# fpga-bank4-inside.net
KiCad netlist of a schematic drawn in Altium Designer
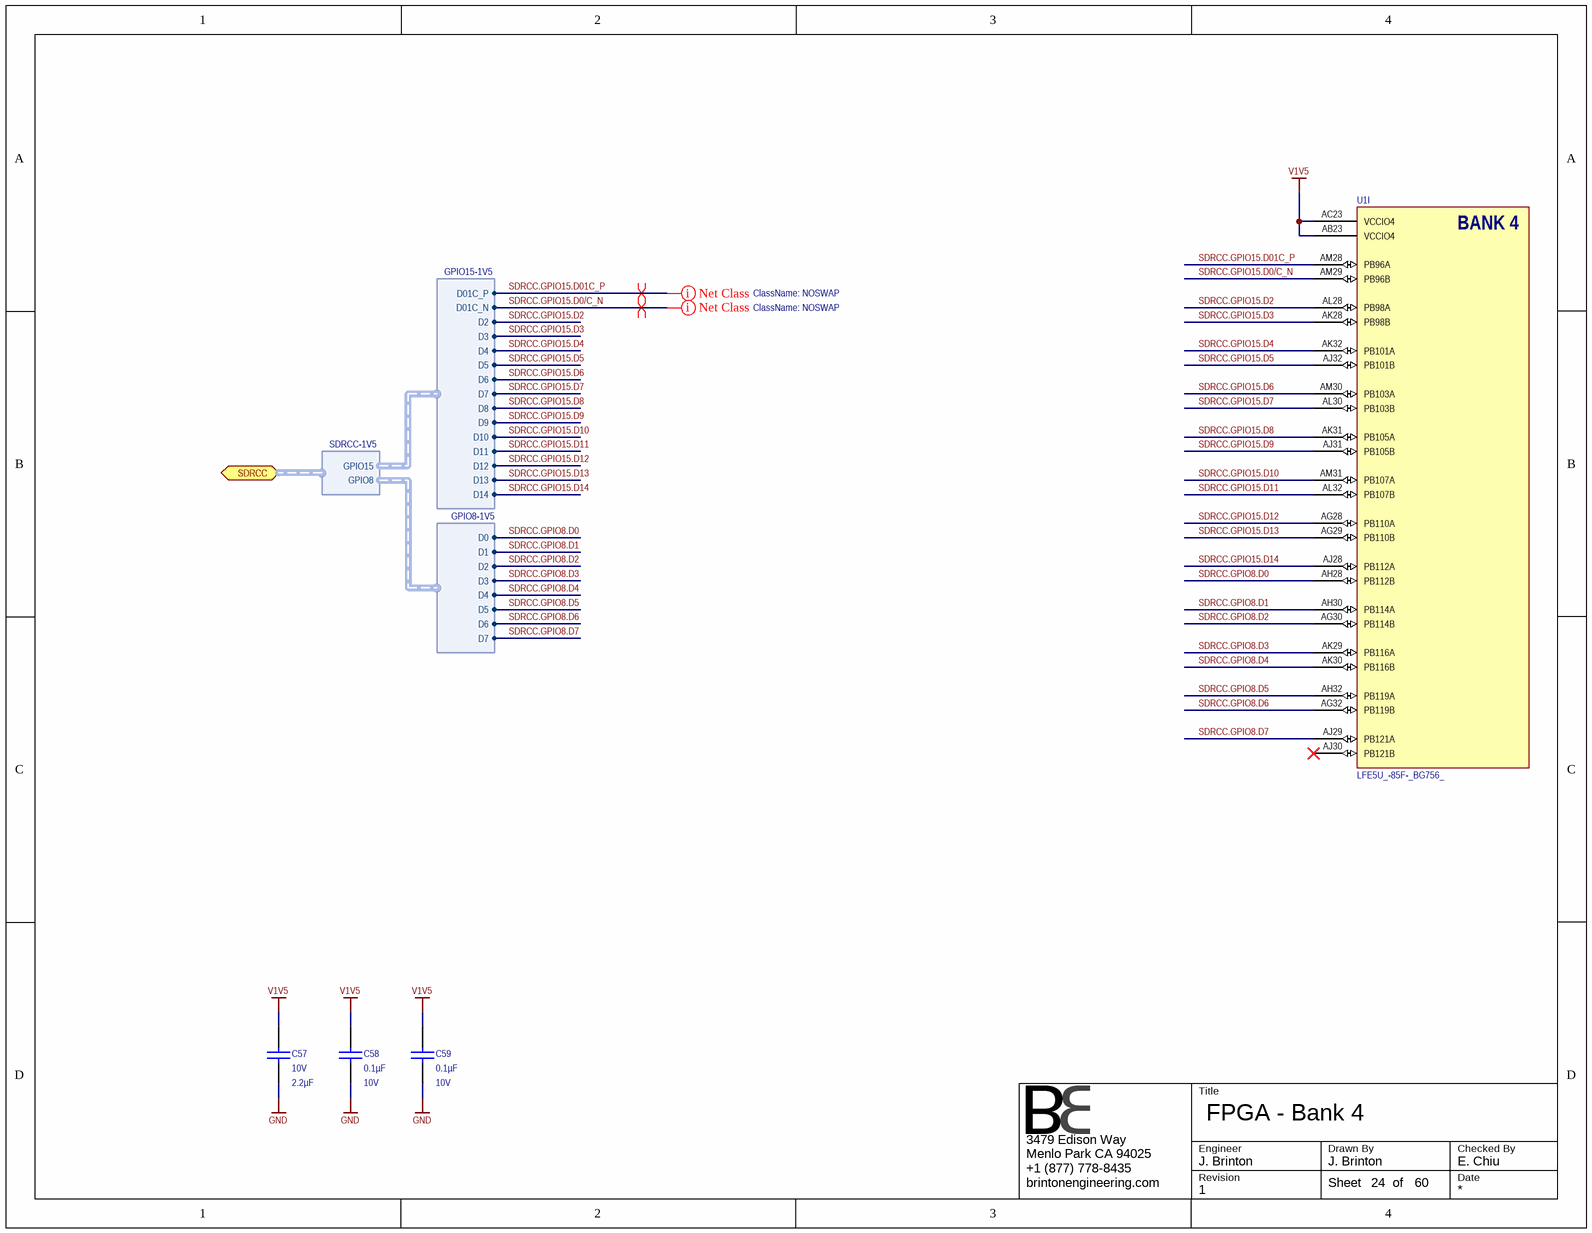
[diagram p0: fpga-bank4-inside.SchDoc]

(export (version "E")
  (design (tool "Eeschema 10.0.6"))
  (components
    (comp (ref "C57")
      (value "GRM188R71A225KE15D")
      (footprint "CAPC1608X90N")
      (description "CAP CER 2.2UF 10V 10% X7R 0603")
      (fields
        (field (name "MANUFACTURER") "Murata Electronics North America")
        (field (name "TOLERANCE") "±10%")
        (field (name "VOLTAGE - RATED") "10V")
        (field (name "CAPACITANCE") "2.2µF")
      )
      (libsource (lib "murata") (part "GRM188R71A225KE15D"))
    )
    (comp (ref "C58")
      (value "GRM155R71A104KA01J")
      (footprint "CAPC1005X56N")
      (description "CAP CER 0.1UF 10V 10% X7R 0402")
      (fields
        (field (name "MANUFACTURER") "Murata Electronics North America")
        (field (name "TOLERANCE") "±10%")
        (field (name "CAPACITANCE") "0.1µF")
        (field (name "VOLTAGE - RATED") "10V")
      )
      (libsource (lib "murata") (part "GRM155R71A104KA01J"))
    )
    (comp (ref "C59")
      (value "GRM155R71A104KA01J")
      (footprint "CAPC1005X56N")
      (description "CAP CER 0.1UF 10V 10% X7R 0402")
      (fields
        (field (name "MANUFACTURER") "Murata Electronics North America")
        (field (name "TOLERANCE") "±10%")
        (field (name "CAPACITANCE") "0.1µF")
        (field (name "VOLTAGE - RATED") "10V")
      )
      (libsource (lib "murata") (part "GRM155R71A104KA01J"))
    )
    (comp (ref "U1")
      (value "LFE5U_-85F-_BG756_")
      (footprint "lattice:caBGA756")
      (description "ECP5 FPGA, 85k LUT, 756-caBGA")
      (fields (field (name "MANUFACTURER") "Lattice Semiconductor"))
      (libsource (lib "lattice") (part "LFE5U_-85F-_BG756_"))
    )
  )
  (nets
    (net (code "4") (name "/SDRCC.GPIO8.D0") (class "Default")
      (node (ref "U1") (pin "AH28") (pinfunction "PB112B_AH28") (pintype "bidirectional"))
    )
    (net (code "5") (name "/SDRCC.GPIO8.D1") (class "Default")
      (node (ref "U1") (pin "AH30") (pinfunction "PB114A_AH30") (pintype "bidirectional"))
    )
    (net (code "6") (name "/SDRCC.GPIO8.D2") (class "Default")
      (node (ref "U1") (pin "AG30") (pinfunction "PB114B_AG30") (pintype "bidirectional"))
    )
    (net (code "7") (name "/SDRCC.GPIO8.D3") (class "Default")
      (node (ref "U1") (pin "AK29") (pinfunction "PB116A_AK29") (pintype "bidirectional"))
    )
    (net (code "8") (name "/SDRCC.GPIO8.D4") (class "Default")
      (node (ref "U1") (pin "AK30") (pinfunction "PB116B_AK30") (pintype "bidirectional"))
    )
    (net (code "9") (name "/SDRCC.GPIO8.D5") (class "Default")
      (node (ref "U1") (pin "AH32") (pinfunction "PB119A_AH32") (pintype "bidirectional"))
    )
    (net (code "10") (name "/SDRCC.GPIO8.D6") (class "Default")
      (node (ref "U1") (pin "AG32") (pinfunction "PB119B_AG32") (pintype "bidirectional"))
    )
    (net (code "11") (name "/SDRCC.GPIO8.D7") (class "Default")
      (node (ref "U1") (pin "AJ29") (pinfunction "PB121A_AJ29") (pintype "bidirectional"))
    )
    (net (code "12") (name "/SDRCC.GPIO15.D0{slash}C_N") (class "Default")
      (node (ref "U1") (pin "AM29") (pinfunction "PB96B_AM29") (pintype "bidirectional"))
    )
    (net (code "13") (name "/SDRCC.GPIO15.D01C_P") (class "Default")
      (node (ref "U1") (pin "AM28") (pinfunction "PB96A_AM28") (pintype "bidirectional"))
    )
    (net (code "14") (name "/SDRCC.GPIO15.D2") (class "Default")
      (node (ref "U1") (pin "AL28") (pinfunction "PB98A_AL28") (pintype "bidirectional"))
    )
    (net (code "15") (name "/SDRCC.GPIO15.D3") (class "Default")
      (node (ref "U1") (pin "AK28") (pinfunction "PB98B_AK28") (pintype "bidirectional"))
    )
    (net (code "16") (name "/SDRCC.GPIO15.D4") (class "Default")
      (node (ref "U1") (pin "AK32") (pinfunction "PB101A_AK32") (pintype "bidirectional"))
    )
    (net (code "17") (name "/SDRCC.GPIO15.D5") (class "Default")
      (node (ref "U1") (pin "AJ32") (pinfunction "PB101B_AJ32") (pintype "bidirectional"))
    )
    (net (code "18") (name "/SDRCC.GPIO15.D6") (class "Default")
      (node (ref "U1") (pin "AM30") (pinfunction "PB103A_AM30") (pintype "bidirectional"))
    )
    (net (code "19") (name "/SDRCC.GPIO15.D7") (class "Default")
      (node (ref "U1") (pin "AL30") (pinfunction "PB103B_AL30") (pintype "bidirectional"))
    )
    (net (code "20") (name "/SDRCC.GPIO15.D8") (class "Default")
      (node (ref "U1") (pin "AK31") (pinfunction "PB105A_AK31") (pintype "bidirectional"))
    )
    (net (code "21") (name "/SDRCC.GPIO15.D9") (class "Default")
      (node (ref "U1") (pin "AJ31") (pinfunction "PB105B_AJ31") (pintype "bidirectional"))
    )
    (net (code "22") (name "/SDRCC.GPIO15.D10") (class "Default")
      (node (ref "U1") (pin "AM31") (pinfunction "PB107A_AM31") (pintype "bidirectional"))
    )
    (net (code "23") (name "/SDRCC.GPIO15.D11") (class "Default")
      (node (ref "U1") (pin "AL32") (pinfunction "PB107B_AL32") (pintype "bidirectional"))
    )
    (net (code "24") (name "/SDRCC.GPIO15.D12") (class "Default")
      (node (ref "U1") (pin "AG28") (pinfunction "PB110A_AG28") (pintype "bidirectional"))
    )
    (net (code "25") (name "/SDRCC.GPIO15.D13") (class "Default")
      (node (ref "U1") (pin "AG29") (pinfunction "PB110B_AG29") (pintype "bidirectional"))
    )
    (net (code "26") (name "/SDRCC.GPIO15.D14") (class "Default")
      (node (ref "U1") (pin "AJ28") (pinfunction "PB112A_AJ28") (pintype "bidirectional"))
    )
    (net (code "30") (name "GND") (class "Default")
      (node (ref "C57") (pin "1") (pinfunction "1_1") (pintype "passive"))
      (node (ref "C58") (pin "1") (pinfunction "1_1") (pintype "passive"))
      (node (ref "C59") (pin "1") (pinfunction "1_1") (pintype "passive"))
    )
    (net (code "31") (name "V1V5") (class "Default")
      (node (ref "C57") (pin "2") (pinfunction "2_2") (pintype "passive"))
      (node (ref "C58") (pin "2") (pinfunction "2_2") (pintype "passive"))
      (node (ref "C59") (pin "2") (pinfunction "2_2") (pintype "passive"))
      (node (ref "U1") (pin "AB23") (pinfunction "VCCIO4_AB23") (pintype "power_in"))
      (node (ref "U1") (pin "AC23") (pinfunction "VCCIO4_AC23") (pintype "power_in"))
    )
    (net (code "32") (name "unconnected-(U1I-PB121B-PadAJ30)") (class "Default")
      (node (ref "U1") (pin "AJ30") (pinfunction "PB121B_AJ30") (pintype "bidirectional+no_connect"))
    )
  )
)
